# V07.net
KiCad netlist of a schematic drawn in EAGLE
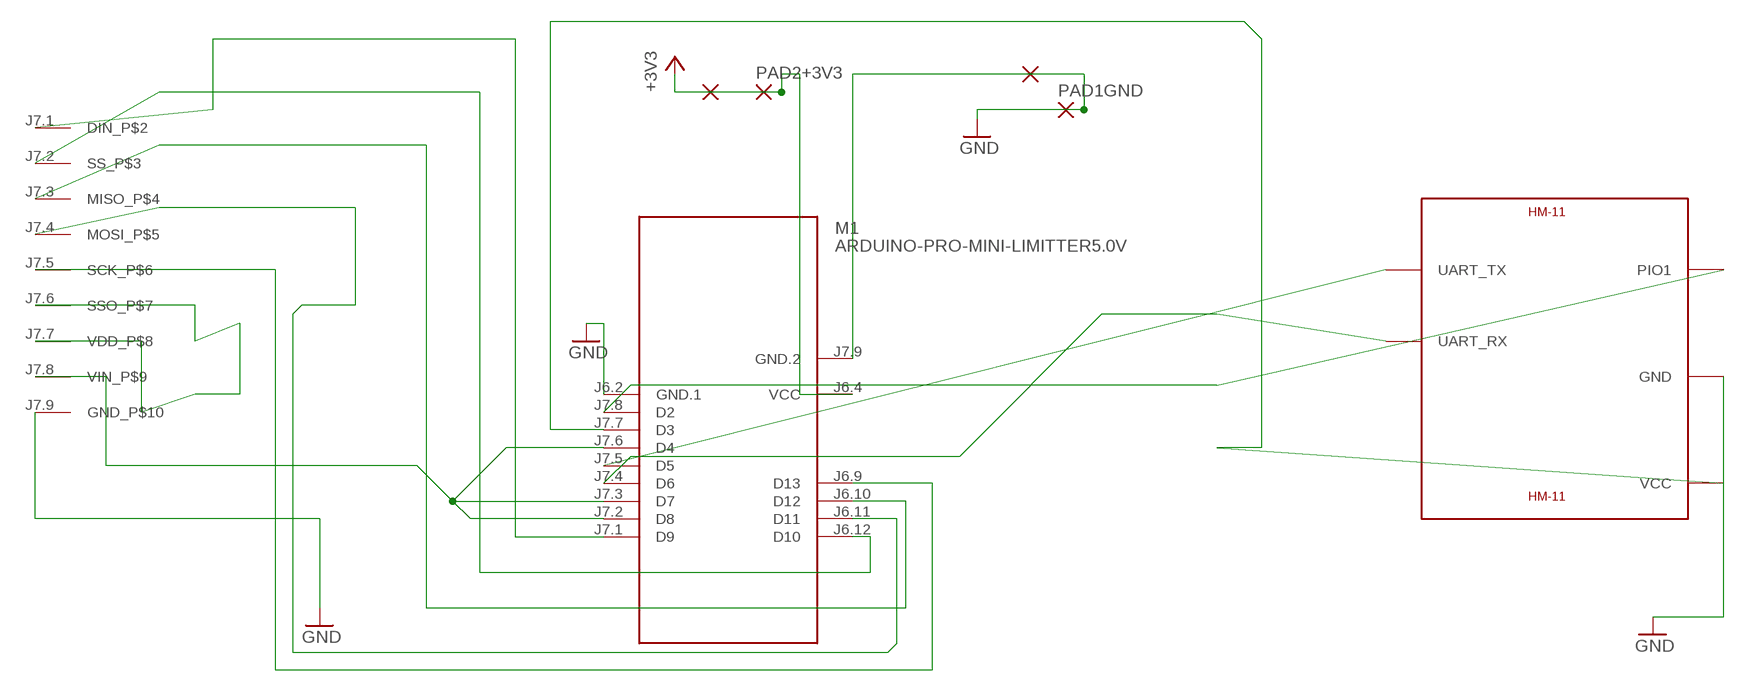
[diagram p0: schematic, sheet 1]

(export (version "E")
  (design (tool "Eeschema 10.0.6"))
  (components
    (comp (ref "M1")
      (value "ARDUINO-PRO-MINI-LIMITTER5.0V")
      (footprint "eagle-import:ARDUINO-PRO-MINI")
      (libsource (lib "eagle-import") (part "ARDUINO-PRO-MINI-LIMITTER5.0V"))
    )
    (comp (ref "PAD1GND")
      (value "1,6/0,8")
      (footprint "eagle-import:1,6_0,8")
      (libsource (lib "eagle-import") (part "1,6/0,8"))
    )
    (comp (ref "PAD2+3V3")
      (value "1,6/0,8")
      (footprint "eagle-import:1,6_0,8")
      (libsource (lib "eagle-import") (part "1,6/0,8"))
    )
    (comp (ref "U$1")
      (value "ARDUINO-9PIN1MM")
      (footprint "eagle-import:ARDUINO-9PIN1MM")
      (libsource (lib "eagle-import") (part "ARDUINO-9PIN1MM"))
    )
    (comp (ref "U$2")
      (value "HM-11")
      (footprint "eagle-import:HM-11")
      (libsource (lib "eagle-import") (part "HM-11"))
    )
  )
  (nets
    (net (code "1") (name "+3V3") (class "Default")
      (node (ref "M1") (pin "J6.4") (pinfunction "VCC_J6.4") (pintype "power_in"))
      (node (ref "PAD2+3V3") (pin "1") (pinfunction "P_1") (pintype "passive"))
    )
    (net (code "2") (name "GND") (class "Default")
      (node (ref "M1") (pin "J6.2") (pinfunction "GND.1_J6.2") (pintype "power_in"))
      (node (ref "M1") (pin "J7.9") (pinfunction "GND.2_J7.9") (pintype "power_in"))
      (node (ref "PAD1GND") (pin "1") (pinfunction "P_1") (pintype "passive"))
      (node (ref "U$1") (pin "J7.9") (pinfunction "GND_P$10_J7.9") (pintype "bidirectional"))
      (node (ref "U$2") (pin "GND") (pinfunction "GND_GND") (pintype "bidirectional"))
    )
    (net (code "3") (name "Net-(M1-D2)") (class "Default")
      (node (ref "M1") (pin "J7.8") (pinfunction "D2_J7.8") (pintype "bidirectional"))
      (node (ref "U$2") (pin "PIO1") (pinfunction "PIO1_PIO1") (pintype "bidirectional"))
    )
    (net (code "4") (name "Net-(M1-D3)") (class "Default")
      (node (ref "M1") (pin "J7.7") (pinfunction "D3_J7.7") (pintype "bidirectional"))
      (node (ref "U$2") (pin "VCC") (pinfunction "VCC_VCC") (pintype "bidirectional"))
    )
    (net (code "5") (name "Net-(M1-D4)") (class "Default")
      (node (ref "M1") (pin "J7.2") (pinfunction "D8_J7.2") (pintype "bidirectional"))
      (node (ref "M1") (pin "J7.3") (pinfunction "D7_J7.3") (pintype "bidirectional"))
      (node (ref "M1") (pin "J7.6") (pinfunction "D4_J7.6") (pintype "bidirectional"))
      (node (ref "U$1") (pin "J7.8") (pinfunction "VIN_P$9_J7.8") (pintype "bidirectional"))
    )
    (net (code "6") (name "Net-(M1-D5)") (class "Default")
      (node (ref "M1") (pin "J7.5") (pinfunction "D5_J7.5") (pintype "bidirectional"))
      (node (ref "U$2") (pin "UART_TX") (pinfunction "UART_TX_UART_TX") (pintype "bidirectional"))
    )
    (net (code "7") (name "Net-(M1-D6)") (class "Default")
      (node (ref "M1") (pin "J7.4") (pinfunction "D6_J7.4") (pintype "bidirectional"))
      (node (ref "U$2") (pin "UART_RX") (pinfunction "UART_RX_UART_RX") (pintype "bidirectional"))
    )
    (net (code "8") (name "Net-(M1-D9)") (class "Default")
      (node (ref "M1") (pin "J7.1") (pinfunction "D9_J7.1") (pintype "bidirectional"))
      (node (ref "U$1") (pin "J7.1") (pinfunction "DIN_P$2_J7.1") (pintype "bidirectional"))
    )
    (net (code "9") (name "Net-(M1-D10)") (class "Default")
      (node (ref "M1") (pin "J6.12") (pinfunction "D10_J6.12") (pintype "bidirectional"))
      (node (ref "U$1") (pin "J7.2") (pinfunction "SS_P$3_J7.2") (pintype "bidirectional"))
    )
    (net (code "10") (name "Net-(M1-D11)") (class "Default")
      (node (ref "M1") (pin "J6.11") (pinfunction "D11_J6.11") (pintype "bidirectional"))
      (node (ref "U$1") (pin "J7.4") (pinfunction "MOSI_P$5_J7.4") (pintype "bidirectional"))
    )
    (net (code "11") (name "Net-(M1-D12)") (class "Default")
      (node (ref "M1") (pin "J6.10") (pinfunction "D12_J6.10") (pintype "bidirectional"))
      (node (ref "U$1") (pin "J7.3") (pinfunction "MISO_P$4_J7.3") (pintype "bidirectional"))
    )
    (net (code "12") (name "Net-(M1-D13)") (class "Default")
      (node (ref "M1") (pin "J6.9") (pinfunction "D13_J6.9") (pintype "bidirectional"))
      (node (ref "U$1") (pin "J7.5") (pinfunction "SCK_P$6_J7.5") (pintype "bidirectional"))
    )
    (net (code "13") (name "Net-(U$1-SSO_P$7)") (class "Default")
      (node (ref "U$1") (pin "J7.6") (pinfunction "SSO_P$7_J7.6") (pintype "bidirectional"))
      (node (ref "U$1") (pin "J7.7") (pinfunction "VDD_P$8_J7.7") (pintype "bidirectional"))
    )
  )
)
